# SwitchingUnit.net
KiCad netlist of a schematic drawn in EAGLE
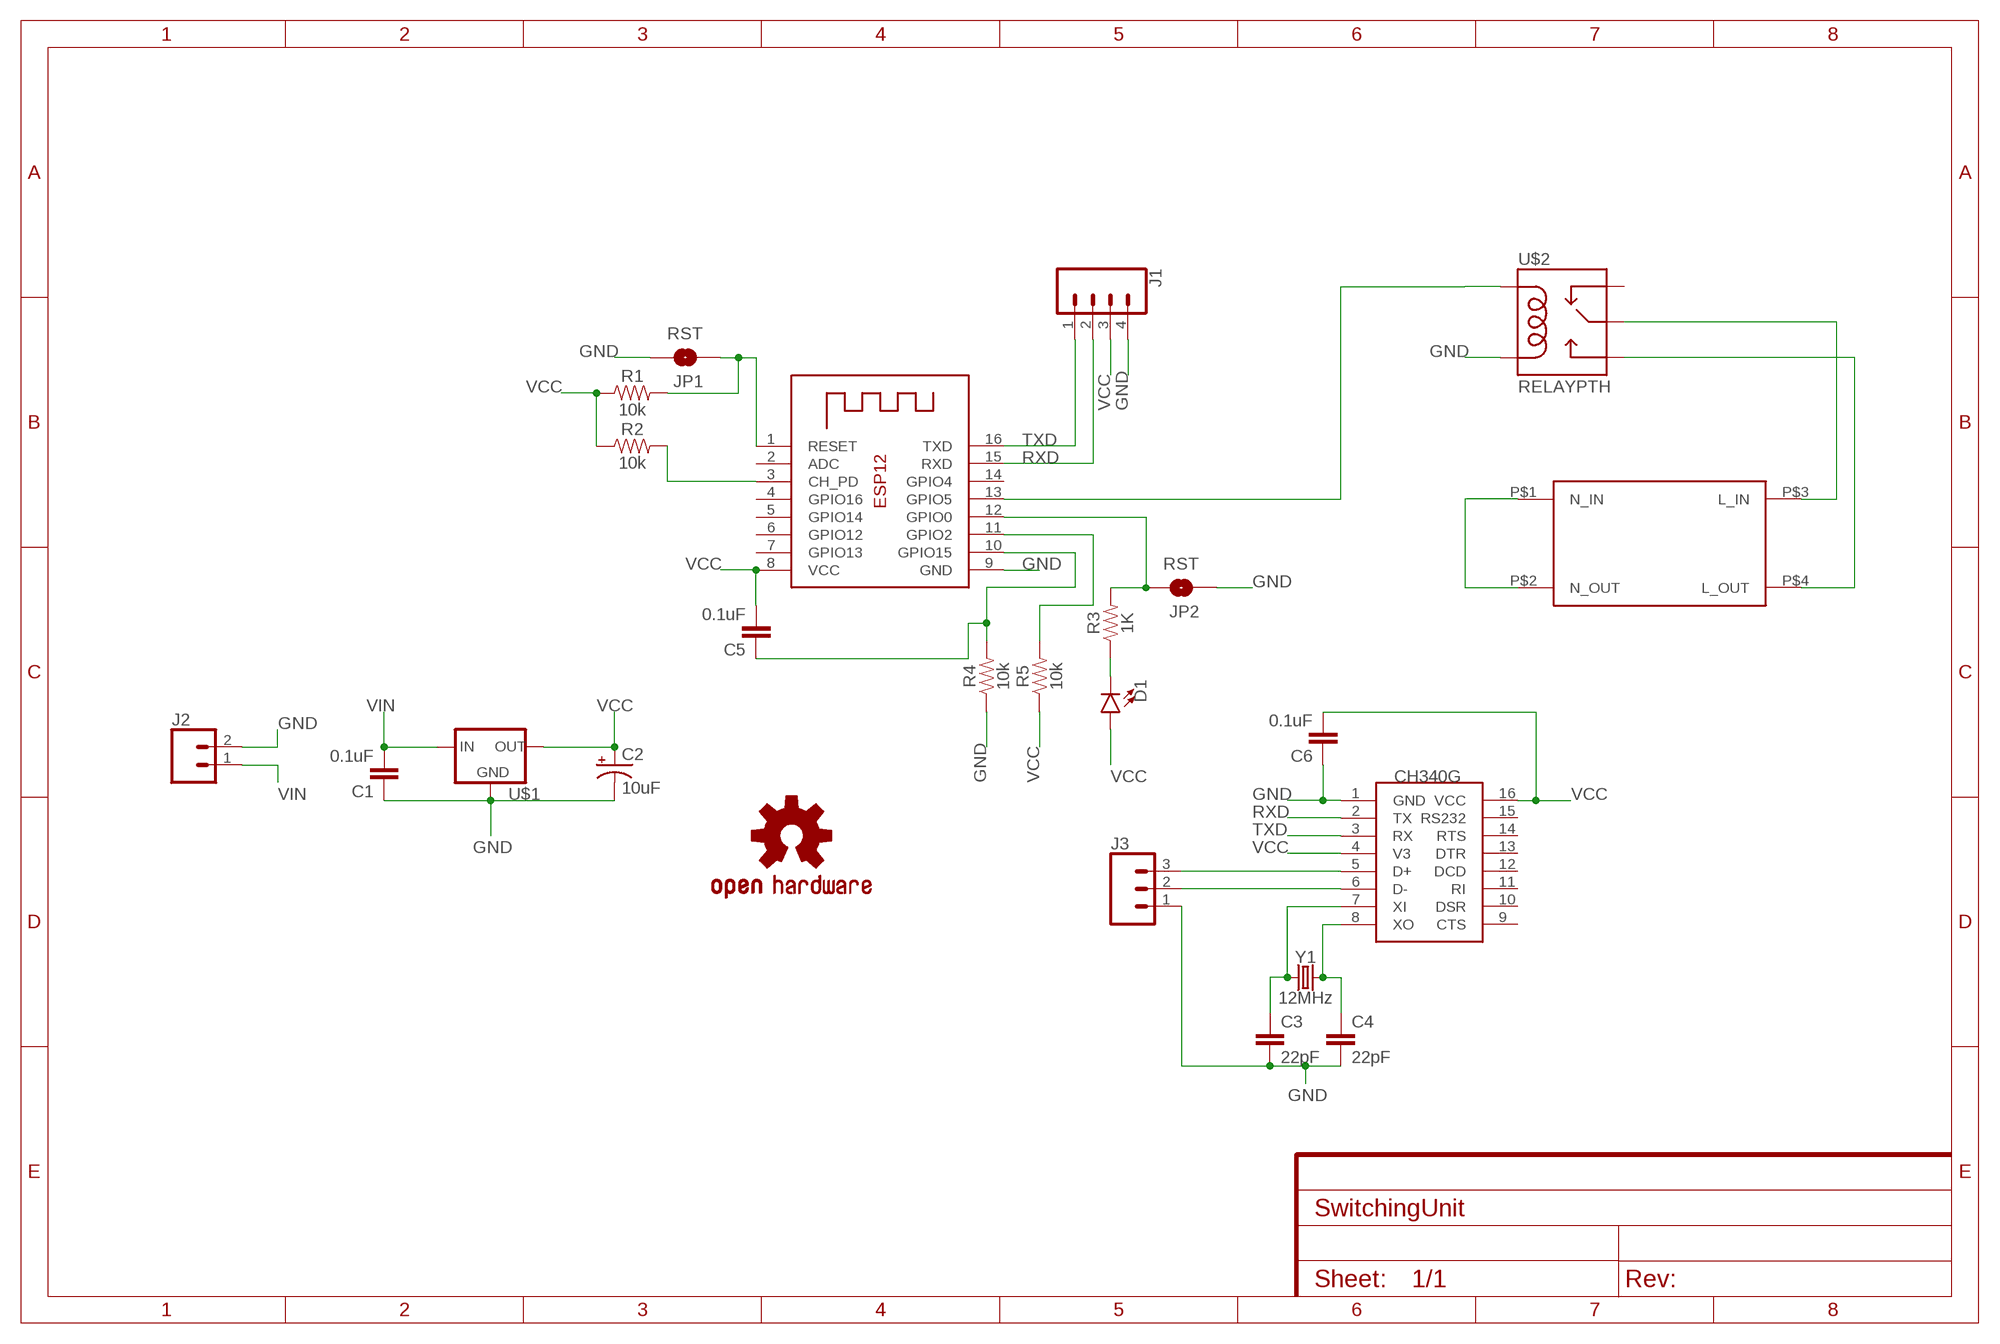
[diagram p0: schematic, sheet 1]

(export (version "E")
  (design (tool "Eeschema 10.0.6"))
  (components
    (comp (ref "C1")
      (value "0.1uF")
      (footprint "eagle-import:CAP-PTH-SMALL-KIT")
      (libsource (lib "eagle-import") (part "0.1UF-KIT-EZ-50V-20%"))
    )
    (comp (ref "C2")
      (value "10uF")
      (footprint "eagle-import:CPOL-RADIAL-2.5MM-5MM")
      (libsource (lib "eagle-import") (part "10UF-POLAR-RADIAL-2.5MM-25V-20%"))
    )
    (comp (ref "C3")
      (value "22pF")
      (footprint "eagle-import:CAP-PTH-2.54")
      (libsource (lib "eagle-import") (part "22PF-PTH-2.54MM-200V-5%"))
    )
    (comp (ref "C4")
      (value "22pF")
      (footprint "eagle-import:CAP-PTH-2.54")
      (libsource (lib "eagle-import") (part "22PF-PTH-2.54MM-200V-5%"))
    )
    (comp (ref "C5")
      (value "0.1uF")
      (footprint "eagle-import:CAP-PTH-SMALL-KIT")
      (libsource (lib "eagle-import") (part "0.1UF-KIT-EZ-50V-20%"))
    )
    (comp (ref "C6")
      (value "0.1uF")
      (footprint "eagle-import:CAP-PTH-SMALL-KIT")
      (libsource (lib "eagle-import") (part "0.1UF-KIT-EZ-50V-20%"))
    )
    (comp (ref "D1")
      (value "LED5MM")
      (footprint "eagle-import:LED_5MM")
      (libsource (lib "eagle-import") (part "LED5MM"))
    )
    (comp (ref "J1")
      (value "CONN_04")
      (footprint "eagle-import:1X04")
      (libsource (lib "eagle-import") (part "CONN_04"))
    )
    (comp (ref "J2")
      (value "CONN_02")
      (footprint "eagle-import:1X02")
      (libsource (lib "eagle-import") (part "CONN_02"))
    )
    (comp (ref "J3")
      (value "CONN_03")
      (footprint "eagle-import:1X03")
      (libsource (lib "eagle-import") (part "CONN_03"))
    )
    (comp (ref "JP1")
      (value "RST")
      (footprint "eagle-import:SMT-JUMPER_2_NO_SILK_ROUND")
      (libsource (lib "eagle-import") (part "JUMPER-SMT_2_NO_SILK_ROUND"))
    )
    (comp (ref "JP2")
      (value "RST")
      (footprint "eagle-import:SMT-JUMPER_2_NO_SILK_ROUND")
      (libsource (lib "eagle-import") (part "JUMPER-SMT_2_NO_SILK_ROUND"))
    )
    (comp (ref "LOGO1")
      (value "OSHW-LOGOL")
      (footprint "eagle-import:OSHW-LOGO-L")
      (libsource (lib "eagle-import") (part "OSHW-LOGOL"))
    )
    (comp (ref "R1")
      (value "10k")
      (footprint "eagle-import:AXIAL-0.3")
      (libsource (lib "eagle-import") (part "10KOHM-HORIZ-1/4W-1%"))
    )
    (comp (ref "R2")
      (value "10k")
      (footprint "eagle-import:AXIAL-0.3")
      (libsource (lib "eagle-import") (part "10KOHM-HORIZ-1/4W-1%"))
    )
    (comp (ref "R3")
      (value "1K")
      (footprint "eagle-import:AXIAL-0.3")
      (libsource (lib "eagle-import") (part "10KOHM-HORIZ-1/4W-1%"))
    )
    (comp (ref "R4")
      (value "10k")
      (footprint "eagle-import:AXIAL-0.3")
      (libsource (lib "eagle-import") (part "10KOHM-HORIZ-1/4W-1%"))
    )
    (comp (ref "R5")
      (value "10k")
      (footprint "eagle-import:AXIAL-0.3")
      (libsource (lib "eagle-import") (part "10KOHM-HORIZ-1/4W-1%"))
    )
    (comp (ref "U$1")
      (value "V_REG_LD1117VXX")
      (footprint "eagle-import:78XXL")
      (libsource (lib "eagle-import") (part "V_REG_LD1117VXX"))
    )
    (comp (ref "U$2")
      (value "RELAYPTH")
      (footprint "eagle-import:SRD-05VDC-SL-C")
      (libsource (lib "eagle-import") (part "RELAYPTH"))
    )
    (comp (ref "U$3")
      (value "MC_MAINS")
      (footprint "eagle-import:MC_MAINS_NEW")
      (libsource (lib "eagle-import") (part "MC_MAINS"))
    )
    (comp (ref "U$4")
      (value "CH340G")
      (footprint "eagle-import:SOIC16")
      (libsource (lib "eagle-import") (part "CH340G"))
    )
    (comp (ref "X1")
      (value "ESP-12")
      (footprint "eagle-import:ESP-12")
      (libsource (lib "eagle-import") (part "ESP-12"))
    )
    (comp (ref "Y1")
      (value "12MHz")
      (footprint "eagle-import:HC49US")
      (libsource (lib "eagle-import") (part "CRYSTAL-16MHZPTH-HC49US"))
    )
  )
  (nets
    (net (code "1") (name "/GND") (class "Default")
      (node (ref "C1") (pin "1") (pinfunction "1_1") (pintype "passive"))
      (node (ref "C2") (pin "2") (pinfunction "-_2") (pintype "passive"))
      (node (ref "C3") (pin "2") (pinfunction "2_2") (pintype "passive"))
      (node (ref "C4") (pin "2") (pinfunction "2_2") (pintype "passive"))
      (node (ref "C6") (pin "1") (pinfunction "1_1") (pintype "passive"))
      (node (ref "J1") (pin "4") (pinfunction "4_4") (pintype "passive"))
      (node (ref "J2") (pin "2") (pinfunction "2_2") (pintype "passive"))
      (node (ref "J3") (pin "1") (pinfunction "1_1") (pintype "passive"))
      (node (ref "JP1") (pin "2") (pinfunction "2_2") (pintype "passive"))
      (node (ref "JP2") (pin "1") (pinfunction "1_1") (pintype "passive"))
      (node (ref "R4") (pin "P$1") (pinfunction "1_P$1") (pintype "passive"))
      (node (ref "U$1") (pin "IN") (pinfunction "GND_IN") (pintype "input"))
      (node (ref "U$2") (pin "COIL0") (pinfunction "COIL0_COIL0") (pintype "bidirectional"))
      (node (ref "U$4") (pin "1") (pinfunction "GND_1") (pintype "bidirectional"))
      (node (ref "X1") (pin "9") (pinfunction "GND_9") (pintype "power_in"))
    )
    (net (code "2") (name "/RXD") (class "Default")
      (node (ref "J1") (pin "2") (pinfunction "2_2") (pintype "passive"))
      (node (ref "U$4") (pin "2") (pinfunction "TX_2") (pintype "bidirectional"))
      (node (ref "X1") (pin "15") (pinfunction "RXD_15") (pintype "input"))
    )
    (net (code "3") (name "/TXD") (class "Default")
      (node (ref "J1") (pin "1") (pinfunction "1_1") (pintype "passive"))
      (node (ref "U$4") (pin "3") (pinfunction "RX_3") (pintype "bidirectional"))
      (node (ref "X1") (pin "16") (pinfunction "TXD_16") (pintype "output"))
    )
    (net (code "4") (name "/VCC") (class "Default")
      (node (ref "C2") (pin "1") (pinfunction "+_1") (pintype "passive"))
      (node (ref "C5") (pin "2") (pinfunction "2_2") (pintype "passive"))
      (node (ref "C6") (pin "2") (pinfunction "2_2") (pintype "passive"))
      (node (ref "D1") (pin "A") (pinfunction "A_A") (pintype "passive"))
      (node (ref "J1") (pin "3") (pinfunction "3_3") (pintype "passive"))
      (node (ref "R1") (pin "P$1") (pinfunction "1_P$1") (pintype "passive"))
      (node (ref "R2") (pin "P$1") (pinfunction "1_P$1") (pintype "passive"))
      (node (ref "R5") (pin "P$1") (pinfunction "1_P$1") (pintype "passive"))
      (node (ref "U$1") (pin "GND") (pinfunction "OUT_GND") (pintype "passive"))
      (node (ref "U$4") (pin "16") (pinfunction "VCC_16") (pintype "bidirectional"))
      (node (ref "U$4") (pin "4") (pinfunction "V3_4") (pintype "bidirectional"))
      (node (ref "X1") (pin "8") (pinfunction "VCC_8") (pintype "power_in"))
    )
    (net (code "5") (name "/VIN") (class "Default")
      (node (ref "C1") (pin "2") (pinfunction "2_2") (pintype "passive"))
      (node (ref "J2") (pin "1") (pinfunction "1_1") (pintype "passive"))
      (node (ref "U$1") (pin "OUT") (pinfunction "IN_OUT") (pintype "input"))
    )
    (net (code "6") (name "Net-(D1-C)") (class "Default")
      (node (ref "D1") (pin "K") (pinfunction "C_K") (pintype "passive"))
      (node (ref "R3") (pin "P$1") (pinfunction "1_P$1") (pintype "passive"))
    )
    (net (code "7") (name "Net-(R1-2)") (class "Default")
      (node (ref "JP1") (pin "1") (pinfunction "1_1") (pintype "passive"))
      (node (ref "R1") (pin "P$2") (pinfunction "2_P$2") (pintype "passive"))
      (node (ref "X1") (pin "1") (pinfunction "RESET_1") (pintype "input"))
    )
    (net (code "8") (name "Net-(R2-2)") (class "Default")
      (node (ref "R2") (pin "P$2") (pinfunction "2_P$2") (pintype "passive"))
      (node (ref "X1") (pin "3") (pinfunction "CH_PD_3") (pintype "input"))
    )
    (net (code "9") (name "Net-(R3-2)") (class "Default")
      (node (ref "JP2") (pin "2") (pinfunction "2_2") (pintype "passive"))
      (node (ref "R3") (pin "P$2") (pinfunction "2_P$2") (pintype "passive"))
      (node (ref "X1") (pin "12") (pinfunction "GPIO0_12") (pintype "bidirectional"))
    )
    (net (code "10") (name "Net-(R4-2)") (class "Default")
      (node (ref "C5") (pin "1") (pinfunction "1_1") (pintype "passive"))
      (node (ref "R4") (pin "P$2") (pinfunction "2_P$2") (pintype "passive"))
      (node (ref "X1") (pin "10") (pinfunction "GPIO15_10") (pintype "bidirectional"))
    )
    (net (code "11") (name "Net-(R5-2)") (class "Default")
      (node (ref "R5") (pin "P$2") (pinfunction "2_P$2") (pintype "passive"))
      (node (ref "X1") (pin "11") (pinfunction "GPIO2_11") (pintype "bidirectional"))
    )
    (net (code "12") (name "Net-(U$3-L_IN)") (class "Default")
      (node (ref "U$2") (pin "SWCOMMON") (pinfunction "SWCOMMON_SWCOMMON") (pintype "bidirectional"))
      (node (ref "U$3") (pin "P$3") (pinfunction "L_IN_P$3") (pintype "bidirectional"))
    )
    (net (code "13") (name "Net-(U$3-L_OUT)") (class "Default")
      (node (ref "U$2") (pin "SWOPEN") (pinfunction "SWOPEN_SWOPEN") (pintype "bidirectional"))
      (node (ref "U$3") (pin "P$4") (pinfunction "L_OUT_P$4") (pintype "bidirectional"))
    )
    (net (code "14") (name "Net-(U$3-N_IN)") (class "Default")
      (node (ref "U$3") (pin "P$1") (pinfunction "N_IN_P$1") (pintype "bidirectional"))
      (node (ref "U$3") (pin "P$2") (pinfunction "N_OUT_P$2") (pintype "bidirectional"))
    )
    (net (code "15") (name "Net-(U$4-D+)") (class "Default")
      (node (ref "J3") (pin "3") (pinfunction "3_3") (pintype "passive"))
      (node (ref "U$4") (pin "5") (pinfunction "D+_5") (pintype "bidirectional"))
    )
    (net (code "16") (name "Net-(U$4-D-)") (class "Default")
      (node (ref "J3") (pin "2") (pinfunction "2_2") (pintype "passive"))
      (node (ref "U$4") (pin "6") (pinfunction "D-_6") (pintype "bidirectional"))
    )
    (net (code "17") (name "Net-(U$4-XI)") (class "Default")
      (node (ref "C3") (pin "1") (pinfunction "1_1") (pintype "passive"))
      (node (ref "U$4") (pin "7") (pinfunction "XI_7") (pintype "bidirectional"))
      (node (ref "Y1") (pin "1") (pinfunction "1_1") (pintype "passive"))
    )
    (net (code "18") (name "Net-(U$4-XO)") (class "Default")
      (node (ref "C4") (pin "1") (pinfunction "1_1") (pintype "passive"))
      (node (ref "U$4") (pin "8") (pinfunction "XO_8") (pintype "bidirectional"))
      (node (ref "Y1") (pin "2") (pinfunction "2_2") (pintype "passive"))
    )
    (net (code "19") (name "Net-(X1-GPIO5)") (class "Default")
      (node (ref "U$2") (pin "COIL1") (pinfunction "COIL1_COIL1") (pintype "bidirectional"))
      (node (ref "X1") (pin "13") (pinfunction "GPIO5_13") (pintype "bidirectional"))
    )
    (net (code "20") (name "unconnected-(U$2-SWCLOSE-PadSWCLOSED)") (class "Default")
      (node (ref "U$2") (pin "SWCLOSED") (pinfunction "SWCLOSE_SWCLOSED") (pintype "bidirectional"))
    )
    (net (code "21") (name "unconnected-(U$4-CTS-Pad9)") (class "Default")
      (node (ref "U$4") (pin "9") (pinfunction "CTS_9") (pintype "bidirectional"))
    )
    (net (code "22") (name "unconnected-(U$4-DCD-Pad12)") (class "Default")
      (node (ref "U$4") (pin "12") (pinfunction "DCD_12") (pintype "bidirectional"))
    )
    (net (code "23") (name "unconnected-(U$4-DSR-Pad10)") (class "Default")
      (node (ref "U$4") (pin "10") (pinfunction "DSR_10") (pintype "bidirectional"))
    )
    (net (code "24") (name "unconnected-(U$4-DTR-Pad13)") (class "Default")
      (node (ref "U$4") (pin "13") (pinfunction "DTR_13") (pintype "bidirectional"))
    )
    (net (code "25") (name "unconnected-(U$4-RI-Pad11)") (class "Default")
      (node (ref "U$4") (pin "11") (pinfunction "RI_11") (pintype "bidirectional"))
    )
    (net (code "26") (name "unconnected-(U$4-RS232-Pad15)") (class "Default")
      (node (ref "U$4") (pin "15") (pinfunction "RS232_15") (pintype "bidirectional"))
    )
    (net (code "27") (name "unconnected-(U$4-RTS-Pad14)") (class "Default")
      (node (ref "U$4") (pin "14") (pinfunction "RTS_14") (pintype "bidirectional"))
    )
    (net (code "28") (name "unconnected-(X1-ADC-Pad2)") (class "Default")
      (node (ref "X1") (pin "2") (pinfunction "ADC_2") (pintype "passive"))
    )
    (net (code "29") (name "unconnected-(X1-GPIO4-Pad14)") (class "Default")
      (node (ref "X1") (pin "14") (pinfunction "GPIO4_14") (pintype "bidirectional"))
    )
    (net (code "30") (name "unconnected-(X1-GPIO12-Pad6)") (class "Default")
      (node (ref "X1") (pin "6") (pinfunction "GPIO12_6") (pintype "bidirectional"))
    )
    (net (code "31") (name "unconnected-(X1-GPIO13-Pad7)") (class "Default")
      (node (ref "X1") (pin "7") (pinfunction "GPIO13_7") (pintype "bidirectional"))
    )
    (net (code "32") (name "unconnected-(X1-GPIO14-Pad5)") (class "Default")
      (node (ref "X1") (pin "5") (pinfunction "GPIO14_5") (pintype "bidirectional"))
    )
    (net (code "33") (name "unconnected-(X1-GPIO16-Pad4)") (class "Default")
      (node (ref "X1") (pin "4") (pinfunction "GPIO16_4") (pintype "bidirectional"))
    )
  )
)
